# DSO_Expendr1_0.net
KiCad netlist of a schematic drawn in EAGLE
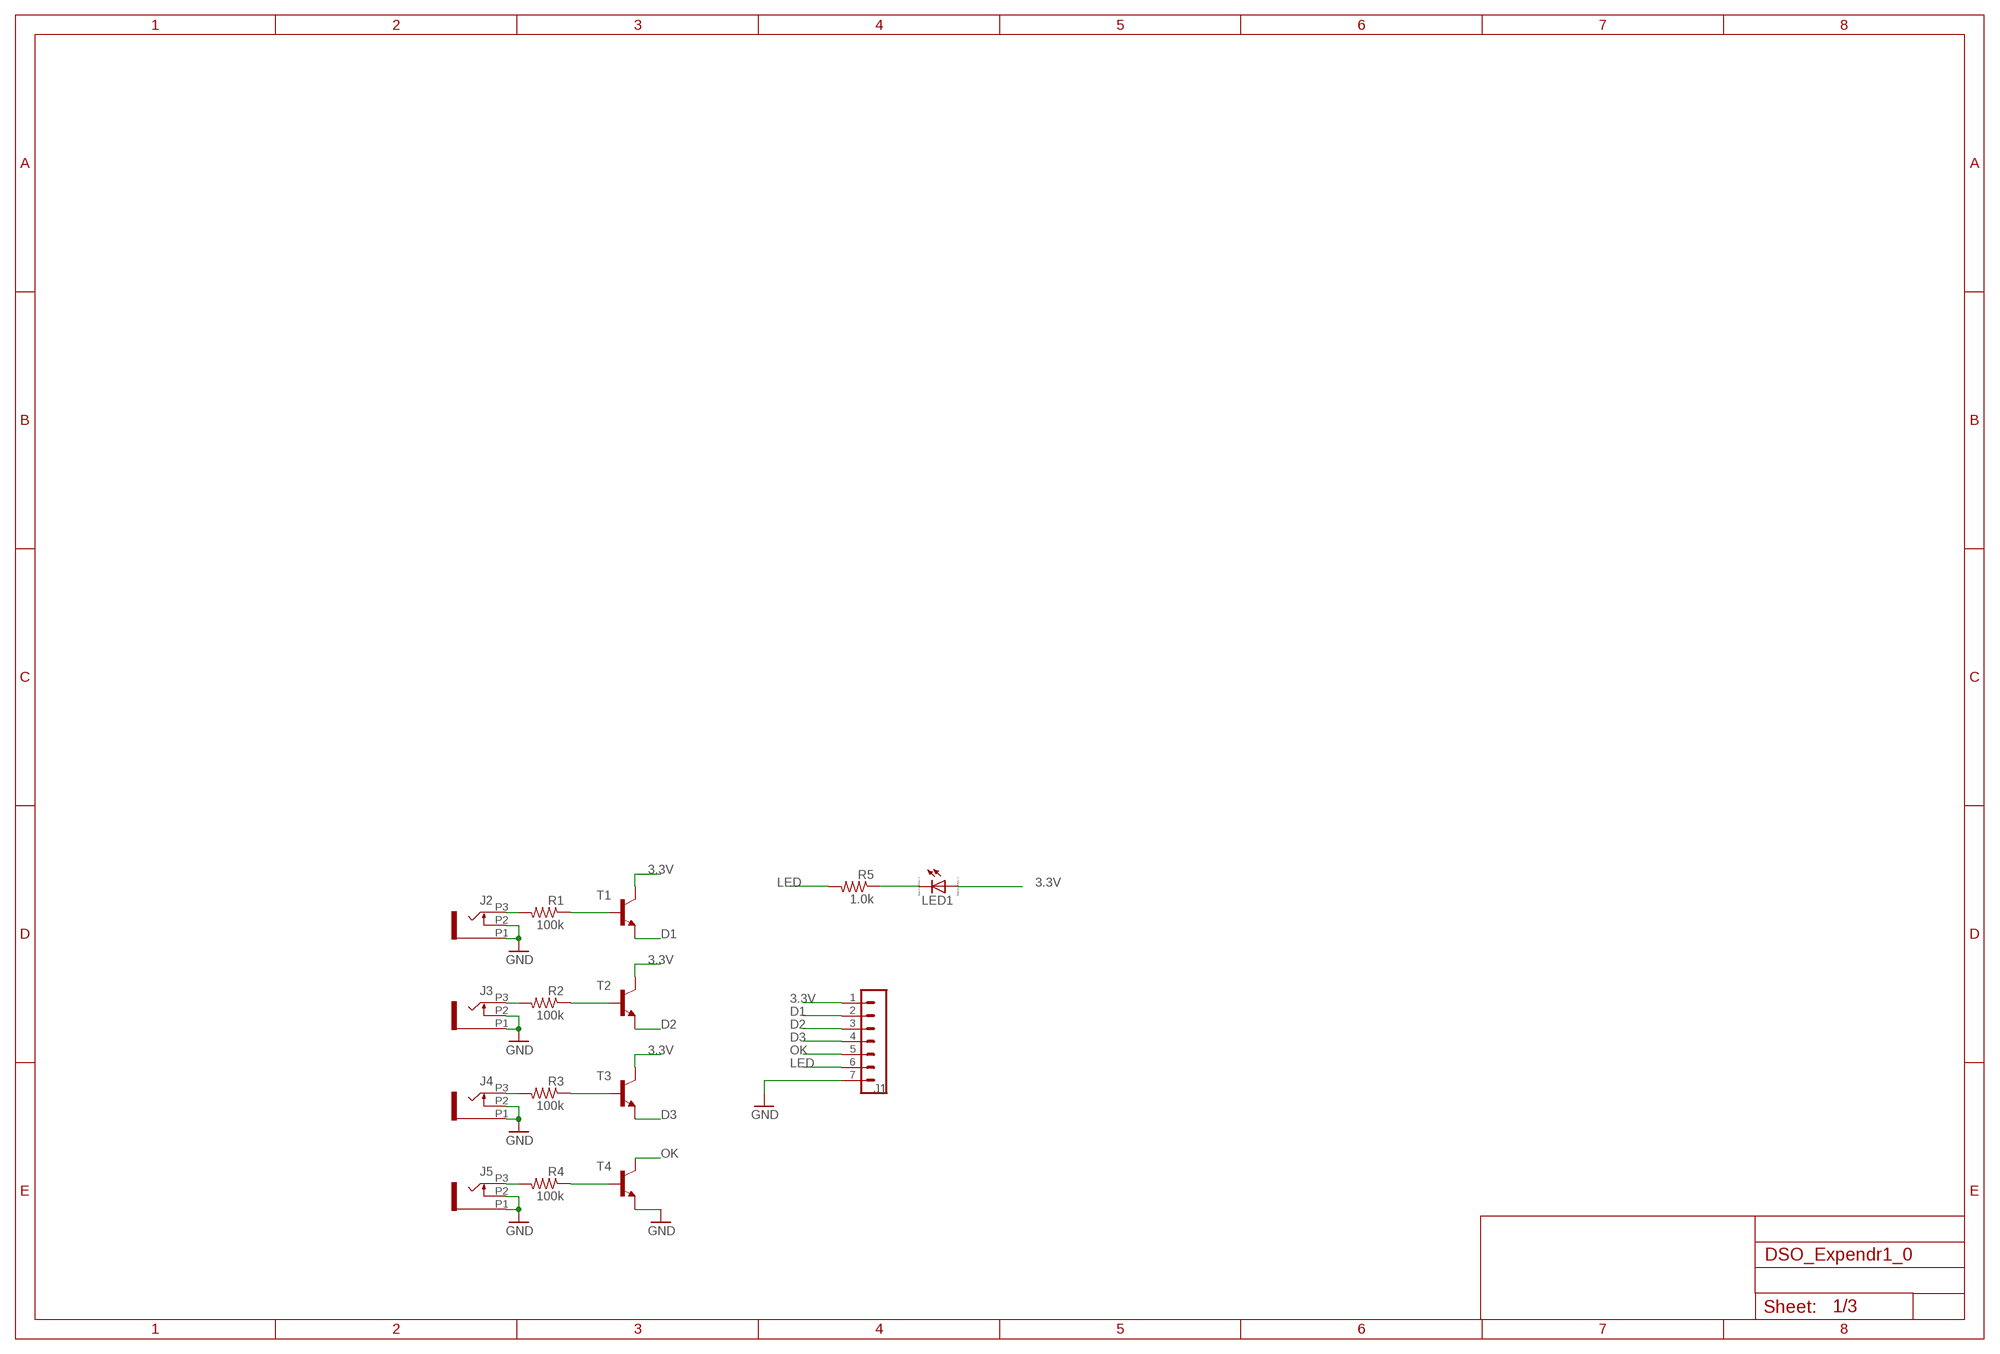
[diagram p0: schematic, sheet 1]

(export (version "E")
  (design (tool "Eeschema 10.0.6"))
  (components
    (comp (ref "J1")
      (value "MA07-1")
      (footprint "eagle-import:MA07-1")
      (libsource (lib "eagle-import") (part "MA07-1"))
    )
    (comp (ref "J2")
      (value "OG-PJ301_PJ301_THONKICONN")
      (footprint "eagle-import:OG-PJ301_WQP_PJ_301M6_NO_HOLE")
      (libsource (lib "eagle-import") (part "OG-PJ301_PJ301_THONKICONN"))
    )
    (comp (ref "J3")
      (value "OG-PJ301_PJ301_THONKICONN")
      (footprint "eagle-import:OG-PJ301_WQP_PJ_301M6_NO_HOLE")
      (libsource (lib "eagle-import") (part "OG-PJ301_PJ301_THONKICONN"))
    )
    (comp (ref "J4")
      (value "OG-PJ301_PJ301_THONKICONN")
      (footprint "eagle-import:OG-PJ301_WQP_PJ_301M6_NO_HOLE")
      (libsource (lib "eagle-import") (part "OG-PJ301_PJ301_THONKICONN"))
    )
    (comp (ref "J5")
      (value "OG-PJ301_PJ301_THONKICONN")
      (footprint "eagle-import:OG-PJ301_WQP_PJ_301M6_NO_HOLE")
      (libsource (lib "eagle-import") (part "OG-PJ301_PJ301_THONKICONN"))
    )
    (comp (ref "LED1")
      (value "LED_E")
      (footprint "eagle-import:LED_1206")
      (libsource (lib "eagle-import") (part "LED_E"))
    )
    (comp (ref "R1")
      (value "100k")
      (footprint "eagle-import:R0805")
      (libsource (lib "eagle-import") (part "R-US_R0805"))
    )
    (comp (ref "R2")
      (value "100k")
      (footprint "eagle-import:R0805")
      (libsource (lib "eagle-import") (part "R-US_R0805"))
    )
    (comp (ref "R3")
      (value "100k")
      (footprint "eagle-import:R0805")
      (libsource (lib "eagle-import") (part "R-US_R0805"))
    )
    (comp (ref "R4")
      (value "100k")
      (footprint "eagle-import:R0805")
      (libsource (lib "eagle-import") (part "R-US_R0805"))
    )
    (comp (ref "R5")
      (value "1.0k")
      (footprint "eagle-import:R0805")
      (libsource (lib "eagle-import") (part "R-US_R0805"))
    )
    (comp (ref "T1")
      (value "MMBT3904LT1-NPN-SOT23-BEC")
      (footprint "eagle-import:SOT23-BEC")
      (libsource (lib "eagle-import") (part "-NPN-SOT23-BECMMBT3904LT1"))
    )
    (comp (ref "T2")
      (value "MMBT3904LT1-NPN-SOT23-BEC")
      (footprint "eagle-import:SOT23-BEC")
      (libsource (lib "eagle-import") (part "-NPN-SOT23-BECMMBT3904LT1"))
    )
    (comp (ref "T3")
      (value "MMBT3904LT1-NPN-SOT23-BEC")
      (footprint "eagle-import:SOT23-BEC")
      (libsource (lib "eagle-import") (part "-NPN-SOT23-BECMMBT3904LT1"))
    )
    (comp (ref "T4")
      (value "MMBT3904LT1-NPN-SOT23-BEC")
      (footprint "eagle-import:SOT23-BEC")
      (libsource (lib "eagle-import") (part "-NPN-SOT23-BECMMBT3904LT1"))
    )
  )
  (nets
    (net (code "1") (name "3.3V") (class "Default")
      (node (ref "J1") (pin "1") (pinfunction "1_1") (pintype "passive"))
      (node (ref "LED1") (pin "A") (pinfunction "A_A") (pintype "passive"))
      (node (ref "T1") (pin "C") (pinfunction "C_C") (pintype "passive"))
      (node (ref "T2") (pin "C") (pinfunction "C_C") (pintype "passive"))
      (node (ref "T3") (pin "C") (pinfunction "C_C") (pintype "passive"))
    )
    (net (code "2") (name "D1") (class "Default")
      (node (ref "J1") (pin "2") (pinfunction "2_2") (pintype "passive"))
      (node (ref "T1") (pin "E") (pinfunction "E_E") (pintype "passive"))
    )
    (net (code "3") (name "D2") (class "Default")
      (node (ref "J1") (pin "3") (pinfunction "3_3") (pintype "passive"))
      (node (ref "T2") (pin "E") (pinfunction "E_E") (pintype "passive"))
    )
    (net (code "4") (name "D3") (class "Default")
      (node (ref "J1") (pin "4") (pinfunction "4_4") (pintype "passive"))
      (node (ref "T3") (pin "E") (pinfunction "E_E") (pintype "passive"))
    )
    (net (code "5") (name "GND") (class "Default")
      (node (ref "J1") (pin "7") (pinfunction "7_7") (pintype "passive"))
      (node (ref "J2") (pin "P1") (pinfunction "1_P1") (pintype "passive"))
      (node (ref "J2") (pin "P2") (pinfunction "2_P2") (pintype "passive"))
      (node (ref "J3") (pin "P1") (pinfunction "1_P1") (pintype "passive"))
      (node (ref "J3") (pin "P2") (pinfunction "2_P2") (pintype "passive"))
      (node (ref "J4") (pin "P1") (pinfunction "1_P1") (pintype "passive"))
      (node (ref "J4") (pin "P2") (pinfunction "2_P2") (pintype "passive"))
      (node (ref "J5") (pin "P1") (pinfunction "1_P1") (pintype "passive"))
      (node (ref "J5") (pin "P2") (pinfunction "2_P2") (pintype "passive"))
      (node (ref "T4") (pin "E") (pinfunction "E_E") (pintype "passive"))
    )
    (net (code "6") (name "LED") (class "Default")
      (node (ref "J1") (pin "6") (pinfunction "6_6") (pintype "passive"))
      (node (ref "R5") (pin "2") (pinfunction "2_2") (pintype "passive"))
    )
    (net (code "7") (name "Net-(J2-3)") (class "Default")
      (node (ref "J2") (pin "P3") (pinfunction "3_P3") (pintype "passive"))
      (node (ref "R1") (pin "2") (pinfunction "2_2") (pintype "passive"))
    )
    (net (code "8") (name "Net-(J3-3)") (class "Default")
      (node (ref "J3") (pin "P3") (pinfunction "3_P3") (pintype "passive"))
      (node (ref "R2") (pin "2") (pinfunction "2_2") (pintype "passive"))
    )
    (net (code "9") (name "Net-(J4-3)") (class "Default")
      (node (ref "J4") (pin "P3") (pinfunction "3_P3") (pintype "passive"))
      (node (ref "R3") (pin "2") (pinfunction "2_2") (pintype "passive"))
    )
    (net (code "10") (name "Net-(J5-3)") (class "Default")
      (node (ref "J5") (pin "P3") (pinfunction "3_P3") (pintype "passive"))
      (node (ref "R4") (pin "2") (pinfunction "2_2") (pintype "passive"))
    )
    (net (code "11") (name "Net-(LED1-PadC)") (class "Default")
      (node (ref "LED1") (pin "C") (pinfunction "C_C") (pintype "passive"))
      (node (ref "R5") (pin "1") (pinfunction "1_1") (pintype "passive"))
    )
    (net (code "12") (name "Net-(R1-Pad1)") (class "Default")
      (node (ref "R1") (pin "1") (pinfunction "1_1") (pintype "passive"))
      (node (ref "T1") (pin "B") (pinfunction "B_B") (pintype "passive"))
    )
    (net (code "13") (name "Net-(R2-Pad1)") (class "Default")
      (node (ref "R2") (pin "1") (pinfunction "1_1") (pintype "passive"))
      (node (ref "T2") (pin "B") (pinfunction "B_B") (pintype "passive"))
    )
    (net (code "14") (name "Net-(R3-Pad1)") (class "Default")
      (node (ref "R3") (pin "1") (pinfunction "1_1") (pintype "passive"))
      (node (ref "T3") (pin "B") (pinfunction "B_B") (pintype "passive"))
    )
    (net (code "15") (name "Net-(R4-Pad1)") (class "Default")
      (node (ref "R4") (pin "1") (pinfunction "1_1") (pintype "passive"))
      (node (ref "T4") (pin "B") (pinfunction "B_B") (pintype "passive"))
    )
    (net (code "16") (name "OK") (class "Default")
      (node (ref "J1") (pin "5") (pinfunction "5_5") (pintype "passive"))
      (node (ref "T4") (pin "C") (pinfunction "C_C") (pintype "passive"))
    )
  )
)
